# COMMS.net
KiCad netlist of a schematic drawn in Altium Designer
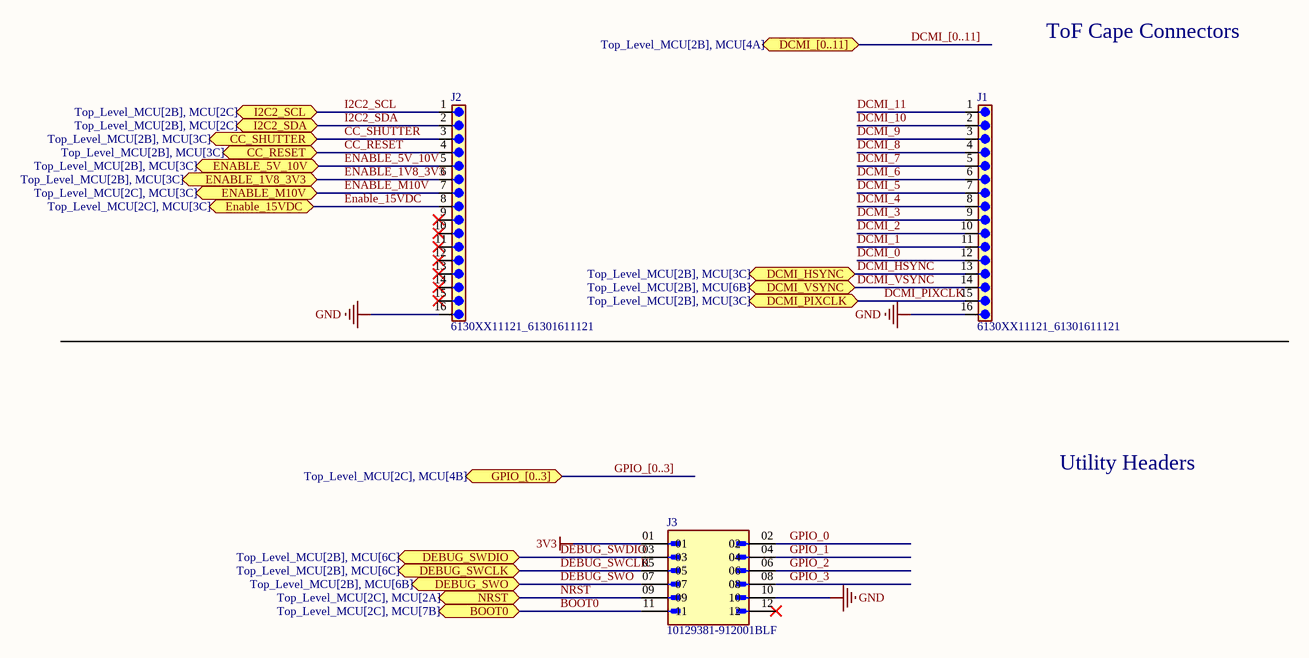
[diagram p0: COMMS.SchDoc]

(export (version "E")
  (design (tool "Eeschema 10.0.6"))
  (components
    (comp (ref "J1")
      (value "6130XX11121_61301611121")
      (footprint "61301611121")
      (fields (field (name "MF") "{'manufacturer': u'Wurth Electronics'}") (field (name "MP") "61301611121"))
      (libsource (lib "6130XX11121_61301611121") (part "6130XX11121_61301611121"))
    )
    (comp (ref "J2")
      (value "6130XX11121_61301611121")
      (footprint "61301611121")
      (fields (field (name "MF") "{'manufacturer': u'Wurth Electronics'}") (field (name "MP") "61301611121"))
      (libsource (lib "6130XX11121_61301611121") (part "6130XX11121_61301611121"))
    )
    (comp (ref "J3")
      (value "10129381-912001BLF")
      (footprint "AMPHENOL_10129381-912001BLF")
      (fields
        (field (name "MF") "Amphenol ICC (FCI)")
        (field (name "DIGI-KEY_PART_NUMBER") "10129381-912001BLF-ND")
      )
      (libsource (lib "10129381-912001BLF") (part "10129381-912001BLF"))
    )
  )
  (nets
    (net (code "1") (name "/BOOT0") (class "Default")
      (node (ref "J3") (pin "11") (pinfunction "11_11") (pintype "passive"))
    )
    (net (code "2") (name "/CC_RESET") (class "Default")
      (node (ref "J2") (pin "4") (pinfunction "4_4") (pintype "passive"))
    )
    (net (code "3") (name "/CC_SHUTTER") (class "Default")
      (node (ref "J2") (pin "3") (pinfunction "3_3") (pintype "passive"))
    )
    (net (code "4") (name "/DCMI_0") (class "Default")
      (node (ref "J1") (pin "12") (pinfunction "12_12") (pintype "passive"))
    )
    (net (code "5") (name "/DCMI_1") (class "Default")
      (node (ref "J1") (pin "11") (pinfunction "11_11") (pintype "passive"))
    )
    (net (code "6") (name "/DCMI_2") (class "Default")
      (node (ref "J1") (pin "10") (pinfunction "10_10") (pintype "passive"))
    )
    (net (code "7") (name "/DCMI_3") (class "Default")
      (node (ref "J1") (pin "9") (pinfunction "9_9") (pintype "passive"))
    )
    (net (code "8") (name "/DCMI_4") (class "Default")
      (node (ref "J1") (pin "8") (pinfunction "8_8") (pintype "passive"))
    )
    (net (code "9") (name "/DCMI_5") (class "Default")
      (node (ref "J1") (pin "7") (pinfunction "7_7") (pintype "passive"))
    )
    (net (code "10") (name "/DCMI_6") (class "Default")
      (node (ref "J1") (pin "6") (pinfunction "6_6") (pintype "passive"))
    )
    (net (code "11") (name "/DCMI_7") (class "Default")
      (node (ref "J1") (pin "5") (pinfunction "5_5") (pintype "passive"))
    )
    (net (code "12") (name "/DCMI_8") (class "Default")
      (node (ref "J1") (pin "4") (pinfunction "4_4") (pintype "passive"))
    )
    (net (code "13") (name "/DCMI_9") (class "Default")
      (node (ref "J1") (pin "3") (pinfunction "3_3") (pintype "passive"))
    )
    (net (code "14") (name "/DCMI_10") (class "Default")
      (node (ref "J1") (pin "2") (pinfunction "2_2") (pintype "passive"))
    )
    (net (code "15") (name "/DCMI_11") (class "Default")
      (node (ref "J1") (pin "1") (pinfunction "1_1") (pintype "passive"))
    )
    (net (code "16") (name "/DCMI_HSYNC") (class "Default")
      (node (ref "J1") (pin "13") (pinfunction "13_13") (pintype "passive"))
    )
    (net (code "17") (name "/DCMI_PIXCLK") (class "Default")
      (node (ref "J1") (pin "15") (pinfunction "15_15") (pintype "passive"))
    )
    (net (code "18") (name "/DCMI_VSYNC") (class "Default")
      (node (ref "J1") (pin "14") (pinfunction "14_14") (pintype "passive"))
    )
    (net (code "20") (name "/DEBUG_SWCLK") (class "Default")
      (node (ref "J3") (pin "05") (pinfunction "05_05") (pintype "passive"))
    )
    (net (code "21") (name "/DEBUG_SWDIO") (class "Default")
      (node (ref "J3") (pin "03") (pinfunction "03_03") (pintype "passive"))
    )
    (net (code "22") (name "/DEBUG_SWO") (class "Default")
      (node (ref "J3") (pin "07") (pinfunction "07_07") (pintype "passive"))
    )
    (net (code "23") (name "/ENABLE_1V8_3V3") (class "Default")
      (node (ref "J2") (pin "6") (pinfunction "6_6") (pintype "passive"))
    )
    (net (code "24") (name "/ENABLE_5V_10V") (class "Default")
      (node (ref "J2") (pin "5") (pinfunction "5_5") (pintype "passive"))
    )
    (net (code "25") (name "/ENABLE_M10V") (class "Default")
      (node (ref "J2") (pin "7") (pinfunction "7_7") (pintype "passive"))
    )
    (net (code "26") (name "/Enable_15VDC") (class "Default")
      (node (ref "J2") (pin "8") (pinfunction "8_8") (pintype "passive"))
    )
    (net (code "27") (name "/GPIO_0") (class "Default")
      (node (ref "J3") (pin "02") (pinfunction "02_02") (pintype "passive"))
    )
    (net (code "28") (name "/GPIO_1") (class "Default")
      (node (ref "J3") (pin "04") (pinfunction "04_04") (pintype "passive"))
    )
    (net (code "29") (name "/GPIO_2") (class "Default")
      (node (ref "J3") (pin "06") (pinfunction "06_06") (pintype "passive"))
    )
    (net (code "30") (name "/GPIO_3") (class "Default")
      (node (ref "J3") (pin "08") (pinfunction "08_08") (pintype "passive"))
    )
    (net (code "32") (name "/I2C2_SCL") (class "Default")
      (node (ref "J2") (pin "1") (pinfunction "1_1") (pintype "passive"))
    )
    (net (code "33") (name "/I2C2_SDA") (class "Default")
      (node (ref "J2") (pin "2") (pinfunction "2_2") (pintype "passive"))
    )
    (net (code "34") (name "/NRST") (class "Default")
      (node (ref "J3") (pin "09") (pinfunction "09_09") (pintype "passive"))
    )
    (net (code "35") (name "3V3") (class "Default")
      (node (ref "J3") (pin "01") (pinfunction "01_01") (pintype "passive"))
    )
    (net (code "36") (name "GND") (class "Default")
      (node (ref "J1") (pin "16") (pinfunction "16_16") (pintype "passive"))
      (node (ref "J2") (pin "16") (pinfunction "16_16") (pintype "passive"))
      (node (ref "J3") (pin "10") (pinfunction "10_10") (pintype "passive"))
    )
    (net (code "37") (name "unconnected-(J2-Pad9)") (class "Default")
      (node (ref "J2") (pin "9") (pinfunction "9_9") (pintype "passive+no_connect"))
    )
    (net (code "38") (name "unconnected-(J2-Pad10)") (class "Default")
      (node (ref "J2") (pin "10") (pinfunction "10_10") (pintype "passive+no_connect"))
    )
    (net (code "39") (name "unconnected-(J2-Pad11)") (class "Default")
      (node (ref "J2") (pin "11") (pinfunction "11_11") (pintype "passive+no_connect"))
    )
    (net (code "40") (name "unconnected-(J2-Pad12)") (class "Default")
      (node (ref "J2") (pin "12") (pinfunction "12_12") (pintype "passive+no_connect"))
    )
    (net (code "41") (name "unconnected-(J2-Pad13)") (class "Default")
      (node (ref "J2") (pin "13") (pinfunction "13_13") (pintype "passive+no_connect"))
    )
    (net (code "42") (name "unconnected-(J2-Pad14)") (class "Default")
      (node (ref "J2") (pin "14") (pinfunction "14_14") (pintype "passive+no_connect"))
    )
    (net (code "43") (name "unconnected-(J2-Pad15)") (class "Default")
      (node (ref "J2") (pin "15") (pinfunction "15_15") (pintype "passive+no_connect"))
    )
    (net (code "44") (name "unconnected-(J3-Pad12)") (class "Default")
      (node (ref "J3") (pin "12") (pinfunction "12_12") (pintype "passive+no_connect"))
    )
  )
)
